# ProcessorSupport.net
KiCad netlist of a schematic drawn in Altium Designer
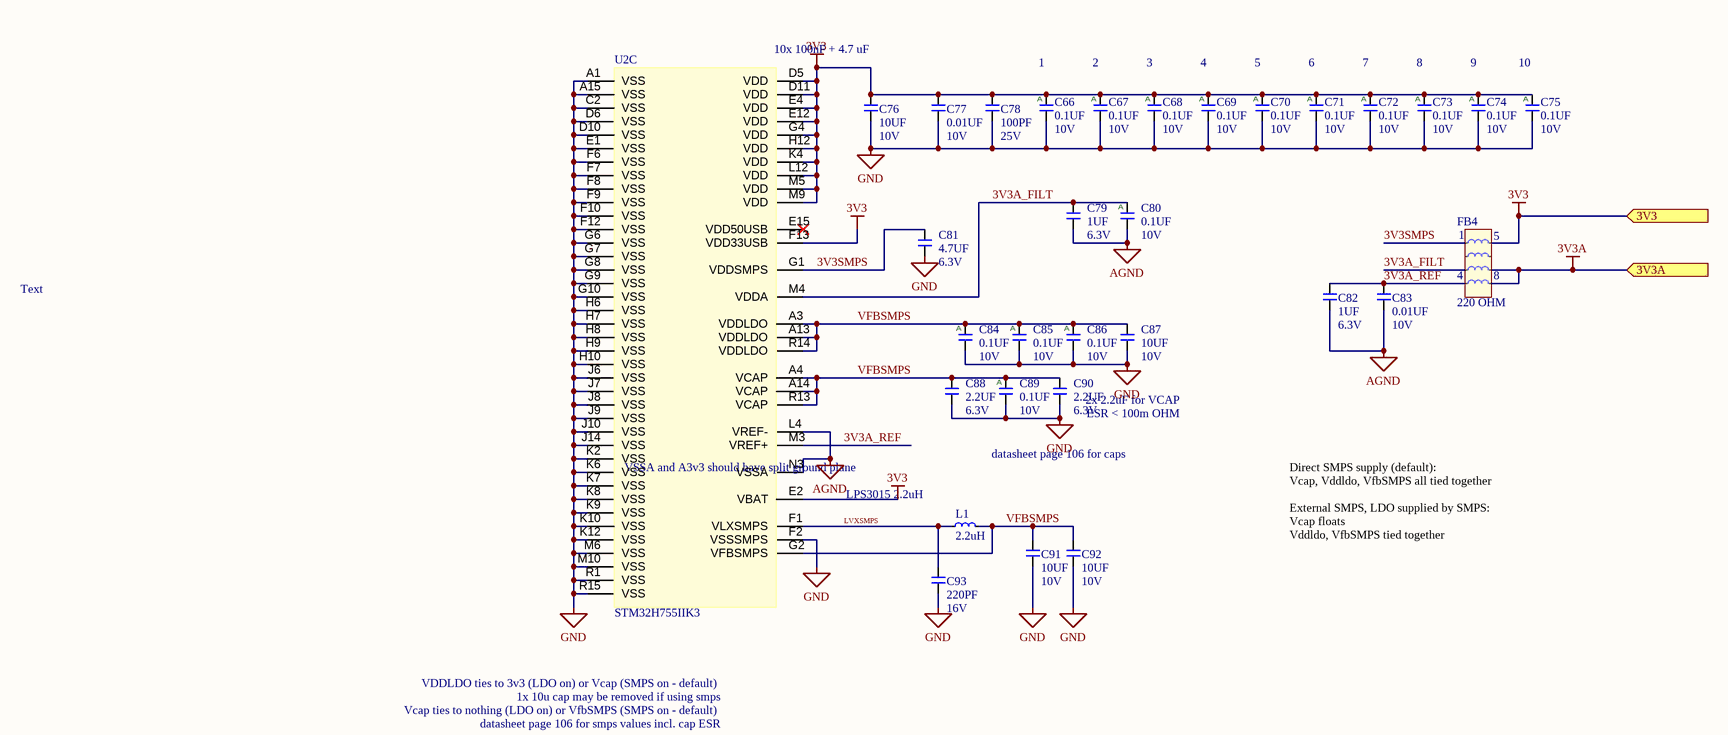
[diagram p0: ProcessorSupport.SchDoc]

(export (version "E")
  (design (tool "Eeschema 10.0.6"))
  (components
    (comp (ref "C66")
      (value "0.1UF")
      (footprint "C0201Y")
      (description "CAP, CER, X6S, 0.1uF, 10V, 10%, 0201, AUTOGRADE")
      (fields (field (name "MFG") "MURATA") (field (name "VOLTAGE") "10V") (field (name "TOLERANCE") "10%"))
      (libsource (lib "AltiumReleaseLibDB") (part "__Template_Cap_Auto"))
    )
    (comp (ref "C67")
      (value "0.1UF")
      (footprint "C0201Y")
      (description "CAP, CER, X6S, 0.1uF, 10V, 10%, 0201, AUTOGRADE")
      (fields (field (name "MFG") "MURATA") (field (name "VOLTAGE") "10V") (field (name "TOLERANCE") "10%"))
      (libsource (lib "AltiumReleaseLibDB") (part "__Template_Cap_Auto"))
    )
    (comp (ref "C68")
      (value "0.1UF")
      (footprint "C0201Y")
      (description "CAP, CER, X6S, 0.1uF, 10V, 10%, 0201, AUTOGRADE")
      (fields (field (name "MFG") "MURATA") (field (name "VOLTAGE") "10V") (field (name "TOLERANCE") "10%"))
      (libsource (lib "AltiumReleaseLibDB") (part "__Template_Cap_Auto"))
    )
    (comp (ref "C69")
      (value "0.1UF")
      (footprint "C0201Y")
      (description "CAP, CER, X6S, 0.1uF, 10V, 10%, 0201, AUTOGRADE")
      (fields (field (name "MFG") "MURATA") (field (name "VOLTAGE") "10V") (field (name "TOLERANCE") "10%"))
      (libsource (lib "AltiumReleaseLibDB") (part "__Template_Cap_Auto"))
    )
    (comp (ref "C70")
      (value "0.1UF")
      (footprint "C0201Y")
      (description "CAP, CER, X6S, 0.1uF, 10V, 10%, 0201, AUTOGRADE")
      (fields (field (name "MFG") "MURATA") (field (name "VOLTAGE") "10V") (field (name "TOLERANCE") "10%"))
      (libsource (lib "AltiumReleaseLibDB") (part "__Template_Cap_Auto"))
    )
    (comp (ref "C71")
      (value "0.1UF")
      (footprint "C0201Y")
      (description "CAP, CER, X6S, 0.1uF, 10V, 10%, 0201, AUTOGRADE")
      (fields (field (name "MFG") "MURATA") (field (name "VOLTAGE") "10V") (field (name "TOLERANCE") "10%"))
      (libsource (lib "AltiumReleaseLibDB") (part "__Template_Cap_Auto"))
    )
    (comp (ref "C72")
      (value "0.1UF")
      (footprint "C0201Y")
      (description "CAP, CER, X6S, 0.1uF, 10V, 10%, 0201, AUTOGRADE")
      (fields (field (name "MFG") "MURATA") (field (name "VOLTAGE") "10V") (field (name "TOLERANCE") "10%"))
      (libsource (lib "AltiumReleaseLibDB") (part "__Template_Cap_Auto"))
    )
    (comp (ref "C73")
      (value "0.1UF")
      (footprint "C0201Y")
      (description "CAP, CER, X6S, 0.1uF, 10V, 10%, 0201, AUTOGRADE")
      (fields (field (name "MFG") "MURATA") (field (name "VOLTAGE") "10V") (field (name "TOLERANCE") "10%"))
      (libsource (lib "AltiumReleaseLibDB") (part "__Template_Cap_Auto"))
    )
    (comp (ref "C74")
      (value "0.1UF")
      (footprint "C0201Y")
      (description "CAP, CER, X6S, 0.1uF, 10V, 10%, 0201, AUTOGRADE")
      (fields (field (name "MFG") "MURATA") (field (name "VOLTAGE") "10V") (field (name "TOLERANCE") "10%"))
      (libsource (lib "AltiumReleaseLibDB") (part "__Template_Cap_Auto"))
    )
    (comp (ref "C75")
      (value "0.1UF")
      (footprint "C0201Y")
      (description "CAP, CER, X6S, 0.1uF, 10V, 10%, 0201, AUTOGRADE")
      (fields (field (name "MFG") "MURATA") (field (name "VOLTAGE") "10V") (field (name "TOLERANCE") "10%"))
      (libsource (lib "AltiumReleaseLibDB") (part "__Template_Cap_Auto"))
    )
    (comp (ref "C76")
      (value "10UF")
      (footprint "C0402")
      (description "CAP, CER, X5R, 10uF, 10V, 20%, 0402, 0.7mm T")
      (fields (field (name "MFG") "SAMSUNG") (field (name "VOLTAGE") "10V") (field (name "TOLERANCE") "20%"))
      (libsource (lib "AltiumReleaseLibDB") (part "__Template_Cap"))
    )
    (comp (ref "C77")
      (value "0.01UF")
      (footprint "C0201Y")
      (description "CAP, CER, X7R, 0.01uF, 10V, 10%, AUTO GRADE, 0201, 0.33mm T")
      (fields (field (name "MFG") "MURATA") (field (name "VOLTAGE") "10V") (field (name "TOLERANCE") "10%"))
      (libsource (lib "AltiumReleaseLibDB") (part "__Template_Cap"))
    )
    (comp (ref "C78")
      (value "100PF")
      (footprint "C0201Y")
      (description "CAP, CER, X7R, 100pF, 25V, 10%, 0201, 0.33mm T")
      (fields (field (name "MFG") "MURATA") (field (name "VOLTAGE") "25V") (field (name "TOLERANCE") "10%"))
      (libsource (lib "AltiumReleaseLibDB") (part "__Template_Cap"))
    )
    (comp (ref "C79")
      (value "1UF")
      (footprint "C0201")
      (description "CAP, CER, X5R, 1uF, 6.3V, 20%, 0201, 0.33mm T")
      (fields (field (name "MFG") "SAMSUNG") (field (name "VOLTAGE") "6.3V") (field (name "TOLERANCE") "20%"))
      (libsource (lib "AltiumReleaseLibDB") (part "__Template_Cap"))
    )
    (comp (ref "C80")
      (value "0.1UF")
      (footprint "C0201Y")
      (description "CAP, CER, X6S, 0.1uF, 10V, 10%, 0201, AUTOGRADE")
      (fields (field (name "MFG") "MURATA") (field (name "VOLTAGE") "10V") (field (name "TOLERANCE") "10%"))
      (libsource (lib "AltiumReleaseLibDB") (part "__Template_Cap_Auto"))
    )
    (comp (ref "C81")
      (value "4.7UF")
      (footprint "C0402")
      (description "CAP, CER, X5R, 4.7uF, 20%, 6.3V, 0402, 0.65mm")
      (fields (field (name "MFG") "TDK") (field (name "VOLTAGE") "6.3V") (field (name "TOLERANCE") "20%"))
      (libsource (lib "AltiumReleaseLibDB") (part "__Template_Cap"))
    )
    (comp (ref "C82")
      (value "1UF")
      (footprint "C0201")
      (description "CAP, CER, X5R, 1uF, 6.3V, 20%, 0201, 0.33mm T")
      (fields (field (name "MFG") "SAMSUNG") (field (name "VOLTAGE") "6.3V") (field (name "TOLERANCE") "20%"))
      (libsource (lib "AltiumReleaseLibDB") (part "__Template_Cap"))
    )
    (comp (ref "C83")
      (value "0.01UF")
      (footprint "C0201Y")
      (description "CAP, CER, X7R, 0.01uF, 10V, 10%, AUTO GRADE, 0201, 0.33mm T")
      (fields (field (name "MFG") "MURATA") (field (name "VOLTAGE") "10V") (field (name "TOLERANCE") "10%"))
      (libsource (lib "AltiumReleaseLibDB") (part "__Template_Cap"))
    )
    (comp (ref "C84")
      (value "0.1UF")
      (footprint "C0201Y")
      (description "CAP, CER, X6S, 0.1uF, 10V, 10%, 0201, AUTOGRADE")
      (fields (field (name "MFG") "MURATA") (field (name "VOLTAGE") "10V") (field (name "TOLERANCE") "10%"))
      (libsource (lib "AltiumReleaseLibDB") (part "__Template_Cap_Auto"))
    )
    (comp (ref "C85")
      (value "0.1UF")
      (footprint "C0201Y")
      (description "CAP, CER, X6S, 0.1uF, 10V, 10%, 0201, AUTOGRADE")
      (fields (field (name "MFG") "MURATA") (field (name "VOLTAGE") "10V") (field (name "TOLERANCE") "10%"))
      (libsource (lib "AltiumReleaseLibDB") (part "__Template_Cap_Auto"))
    )
    (comp (ref "C86")
      (value "0.1UF")
      (footprint "C0201Y")
      (description "CAP, CER, X6S, 0.1uF, 10V, 10%, 0201, AUTOGRADE")
      (fields (field (name "MFG") "MURATA") (field (name "VOLTAGE") "10V") (field (name "TOLERANCE") "10%"))
      (libsource (lib "AltiumReleaseLibDB") (part "__Template_Cap_Auto"))
    )
    (comp (ref "C87")
      (value "10UF")
      (footprint "C0402")
      (description "CAP, CER, X5R, 10uF, 10V, 20%, 0402, 0.7mm T")
      (fields (field (name "MFG") "SAMSUNG") (field (name "VOLTAGE") "10V") (field (name "TOLERANCE") "20%"))
      (libsource (lib "AltiumReleaseLibDB") (part "__Template_Cap"))
    )
    (comp (ref "C88")
      (value "2.2UF")
      (footprint "C0201")
      (description "CAP, CER, X5R, 2.2uF, 6.3V, 20%, 0201, 0.39mm T")
      (fields (field (name "MFG") "SAMSUNG") (field (name "VOLTAGE") "6.3V") (field (name "TOLERANCE") "20%"))
      (libsource (lib "AltiumReleaseLibDB") (part "__Template_Cap"))
    )
    (comp (ref "C89")
      (value "0.1UF")
      (footprint "C0201Y")
      (description "CAP, CER, X6S, 0.1uF, 10V, 10%, 0201, AUTOGRADE")
      (fields (field (name "MFG") "MURATA") (field (name "VOLTAGE") "10V") (field (name "TOLERANCE") "10%"))
      (libsource (lib "AltiumReleaseLibDB") (part "__Template_Cap_Auto"))
    )
    (comp (ref "C90")
      (value "2.2UF")
      (footprint "C0201")
      (description "CAP, CER, X5R, 2.2uF, 6.3V, 20%, 0201, 0.39mm T")
      (fields (field (name "MFG") "SAMSUNG") (field (name "VOLTAGE") "6.3V") (field (name "TOLERANCE") "20%"))
      (libsource (lib "AltiumReleaseLibDB") (part "__Template_Cap"))
    )
    (comp (ref "C91")
      (value "10UF")
      (footprint "C0402")
      (description "CAP, CER, X5R, 10uF, 10V, 20%, 0402, 0.7mm T")
      (fields (field (name "MFG") "SAMSUNG") (field (name "VOLTAGE") "10V") (field (name "TOLERANCE") "20%"))
      (libsource (lib "AltiumReleaseLibDB") (part "__Template_Cap"))
    )
    (comp (ref "C92")
      (value "10UF")
      (footprint "C0402")
      (description "CAP, CER, X5R, 10uF, 10V, 20%, 0402, 0.7mm T")
      (fields (field (name "MFG") "SAMSUNG") (field (name "VOLTAGE") "10V") (field (name "TOLERANCE") "20%"))
      (libsource (lib "AltiumReleaseLibDB") (part "__Template_Cap"))
    )
    (comp (ref "C93")
      (value "220PF")
      (footprint "C0201Y")
      (description "CAP, CER, X7R, 220pF, 16V, 10%, 0201, 0.33mm T")
      (fields (field (name "MFG") "MURATA") (field (name "VOLTAGE") "16V") (field (name "TOLERANCE") "10%"))
      (libsource (lib "AltiumReleaseLibDB") (part "__Template_Cap"))
    )
    (comp (ref "FB4")
      (value "220 OHM")
      (footprint "FB_ARRAY_BLA31AG221SN4D")
      (description "FERRITE, BEAD, 220 OHM, 150mA, DCR 0.25 MAX, 1206")
      (fields (field (name "MFG") "Murata Electronics") (field (name "Comment") "FB_ARRAY_BLA31AG221SN4D"))
      (libsource (lib "AltiumReleaseLibDB") (part "FB_ARRAY_BLA31AG221SN4D"))
    )
    (comp (ref "L1")
      (value "2.2uH")
      (footprint "IND_LPS3015-152MRB")
      (description "IND, WIREWOUND, SHIELDED, 2.2uH, 2.1A, 20%, DCR 0.11, SMD, AUTOGRADE")
      (fields (field (name "MFG") "COILCRAFT") (field (name "TOLERANCE") "20%"))
      (libsource (lib "AltiumReleaseLibDB") (part "__Template_Inductor"))
    )
    (comp (ref "U2")
      (value "MCU_STM32H755IIK3")
      (footprint "BGS201C65P15X15_1000X1000X60")
      (description "IC, MCU, STM32H755xI, ARM, 32-BIT, 240MHZ, 128 I/O, 2MB, FLASH, 1.62V TO 3.6V, UFBGA-201")
      (fields (field (name "MFG") "STMicroelectronics") (field (name "MFG P/N") "STM32H755IIK3"))
      (libsource (lib "AltiumReleaseLibDB") (part "MCU_STM32H755IIK3"))
    )
  )
  (nets
    (net (code "1") (name "/3V3A_FILT") (class "Default")
      (node (ref "C79") (pin "1") (pintype "passive"))
      (node (ref "C80") (pin "1") (pintype "passive"))
      (node (ref "FB4") (pin "3") (pinfunction "3_3") (pintype "passive"))
      (node (ref "U2") (pin "M4") (pinfunction "VDDA_M4") (pintype "power_in"))
    )
    (net (code "2") (name "/3V3A_REF") (class "Default")
      (node (ref "C82") (pin "1") (pintype "passive"))
      (node (ref "C83") (pin "1") (pintype "passive"))
      (node (ref "FB4") (pin "4") (pinfunction "4_4") (pintype "passive"))
      (node (ref "U2") (pin "M3") (pinfunction "VREF+_M3") (pintype "power_in"))
    )
    (net (code "3") (name "/3V3SMPS") (class "Default")
      (node (ref "C81") (pin "1") (pintype "passive"))
      (node (ref "FB4") (pin "1") (pinfunction "1_1") (pintype "passive"))
      (node (ref "U2") (pin "G1") (pinfunction "VDDSMPS_G1") (pintype "power_in"))
    )
    (net (code "4") (name "/LVXSMPS") (class "Default")
      (node (ref "C93") (pin "1") (pintype "passive"))
      (node (ref "L1") (pin "1") (pintype "passive"))
      (node (ref "U2") (pin "F1") (pinfunction "VLXSMPS_F1") (pintype "power_in"))
    )
    (net (code "5") (name "/VFBSMPS") (class "Default")
      (node (ref "C84") (pin "1") (pintype "passive"))
      (node (ref "C85") (pin "1") (pintype "passive"))
      (node (ref "C86") (pin "1") (pintype "passive"))
      (node (ref "C87") (pin "1") (pintype "passive"))
      (node (ref "C88") (pin "1") (pintype "passive"))
      (node (ref "C89") (pin "1") (pintype "passive"))
      (node (ref "C90") (pin "1") (pintype "passive"))
      (node (ref "C91") (pin "2") (pintype "passive"))
      (node (ref "C92") (pin "2") (pintype "passive"))
      (node (ref "L1") (pin "2") (pintype "passive"))
      (node (ref "U2") (pin "A13") (pinfunction "VDDLDO_A13") (pintype "power_in"))
      (node (ref "U2") (pin "A14") (pinfunction "VCAP_A14") (pintype "power_in"))
      (node (ref "U2") (pin "A3") (pinfunction "VDDLDO_A3") (pintype "power_in"))
      (node (ref "U2") (pin "A4") (pinfunction "VCAP_A4") (pintype "power_in"))
      (node (ref "U2") (pin "G2") (pinfunction "VFBSMPS_G2") (pintype "power_in"))
      (node (ref "U2") (pin "R13") (pinfunction "VCAP_R13") (pintype "power_in"))
      (node (ref "U2") (pin "R14") (pinfunction "VDDLDO_R14") (pintype "power_in"))
    )
    (net (code "6") (name "3V3") (class "Default")
      (node (ref "C66") (pin "1") (pintype "passive"))
      (node (ref "C67") (pin "1") (pintype "passive"))
      (node (ref "C68") (pin "1") (pintype "passive"))
      (node (ref "C69") (pin "1") (pintype "passive"))
      (node (ref "C70") (pin "1") (pintype "passive"))
      (node (ref "C71") (pin "1") (pintype "passive"))
      (node (ref "C72") (pin "1") (pintype "passive"))
      (node (ref "C73") (pin "1") (pintype "passive"))
      (node (ref "C74") (pin "1") (pintype "passive"))
      (node (ref "C75") (pin "1") (pintype "passive"))
      (node (ref "C76") (pin "1") (pintype "passive"))
      (node (ref "C77") (pin "1") (pintype "passive"))
      (node (ref "C78") (pin "1") (pintype "passive"))
      (node (ref "FB4") (pin "5") (pinfunction "5_5") (pintype "passive"))
      (node (ref "U2") (pin "D11") (pinfunction "VDD_D11") (pintype "power_in"))
      (node (ref "U2") (pin "D5") (pinfunction "VDD_D5") (pintype "power_in"))
      (node (ref "U2") (pin "E12") (pinfunction "VDD_E12") (pintype "power_in"))
      (node (ref "U2") (pin "E2") (pinfunction "VBAT_E2") (pintype "power_in"))
      (node (ref "U2") (pin "E4") (pinfunction "VDD_E4") (pintype "power_in"))
      (node (ref "U2") (pin "F13") (pinfunction "VDD33USB_F13") (pintype "power_in"))
      (node (ref "U2") (pin "G4") (pinfunction "VDD_G4") (pintype "power_in"))
      (node (ref "U2") (pin "H12") (pinfunction "VDD_H12") (pintype "power_in"))
      (node (ref "U2") (pin "K4") (pinfunction "VDD_K4") (pintype "power_in"))
      (node (ref "U2") (pin "L12") (pinfunction "VDD_L12") (pintype "power_in"))
      (node (ref "U2") (pin "M5") (pinfunction "VDD_M5") (pintype "power_in"))
      (node (ref "U2") (pin "M9") (pinfunction "VDD_M9") (pintype "power_in"))
    )
    (net (code "7") (name "3V3A") (class "Default")
      (node (ref "FB4") (pin "7") (pinfunction "7_7") (pintype "passive"))
      (node (ref "FB4") (pin "8") (pinfunction "8_8") (pintype "passive"))
    )
    (net (code "8") (name "AGND") (class "Default")
      (node (ref "C79") (pin "2") (pintype "passive"))
      (node (ref "C80") (pin "2") (pintype "passive"))
      (node (ref "C82") (pin "2") (pintype "passive"))
      (node (ref "C83") (pin "2") (pintype "passive"))
      (node (ref "U2") (pin "L4") (pinfunction "VREF-_L4") (pintype "power_in"))
      (node (ref "U2") (pin "N3") (pinfunction "VSSA_N3") (pintype "power_in"))
    )
    (net (code "9") (name "GND") (class "Default")
      (node (ref "C66") (pin "2") (pintype "passive"))
      (node (ref "C67") (pin "2") (pintype "passive"))
      (node (ref "C68") (pin "2") (pintype "passive"))
      (node (ref "C69") (pin "2") (pintype "passive"))
      (node (ref "C70") (pin "2") (pintype "passive"))
      (node (ref "C71") (pin "2") (pintype "passive"))
      (node (ref "C72") (pin "2") (pintype "passive"))
      (node (ref "C73") (pin "2") (pintype "passive"))
      (node (ref "C74") (pin "2") (pintype "passive"))
      (node (ref "C75") (pin "2") (pintype "passive"))
      (node (ref "C76") (pin "2") (pintype "passive"))
      (node (ref "C77") (pin "2") (pintype "passive"))
      (node (ref "C78") (pin "2") (pintype "passive"))
      (node (ref "C81") (pin "2") (pintype "passive"))
      (node (ref "C84") (pin "2") (pintype "passive"))
      (node (ref "C85") (pin "2") (pintype "passive"))
      (node (ref "C86") (pin "2") (pintype "passive"))
      (node (ref "C87") (pin "2") (pintype "passive"))
      (node (ref "C88") (pin "2") (pintype "passive"))
      (node (ref "C89") (pin "2") (pintype "passive"))
      (node (ref "C90") (pin "2") (pintype "passive"))
      (node (ref "C91") (pin "1") (pintype "passive"))
      (node (ref "C92") (pin "1") (pintype "passive"))
      (node (ref "C93") (pin "2") (pintype "passive"))
      (node (ref "U2") (pin "A1") (pinfunction "VSS_A1") (pintype "power_in"))
      (node (ref "U2") (pin "A15") (pinfunction "VSS_A15") (pintype "power_in"))
      (node (ref "U2") (pin "C2") (pinfunction "VSS_C2") (pintype "power_in"))
      (node (ref "U2") (pin "D10") (pinfunction "VSS_D10") (pintype "power_in"))
      (node (ref "U2") (pin "D6") (pinfunction "VSS_D6") (pintype "power_in"))
      (node (ref "U2") (pin "E1") (pinfunction "VSS_E1") (pintype "power_in"))
      (node (ref "U2") (pin "F10") (pinfunction "VSS_F10") (pintype "power_in"))
      (node (ref "U2") (pin "F12") (pinfunction "VSS_F12") (pintype "power_in"))
      (node (ref "U2") (pin "F2") (pinfunction "VSSSMPS_F2") (pintype "power_in"))
      (node (ref "U2") (pin "F6") (pinfunction "VSS_F6") (pintype "power_in"))
      (node (ref "U2") (pin "F7") (pinfunction "VSS_F7") (pintype "power_in"))
      (node (ref "U2") (pin "F8") (pinfunction "VSS_F8") (pintype "power_in"))
      (node (ref "U2") (pin "F9") (pinfunction "VSS_F9") (pintype "power_in"))
      (node (ref "U2") (pin "G10") (pinfunction "VSS_G10") (pintype "power_in"))
      (node (ref "U2") (pin "G6") (pinfunction "VSS_G6") (pintype "power_in"))
      (node (ref "U2") (pin "G7") (pinfunction "VSS_G7") (pintype "power_in"))
      (node (ref "U2") (pin "G8") (pinfunction "VSS_G8") (pintype "power_in"))
      (node (ref "U2") (pin "G9") (pinfunction "VSS_G9") (pintype "power_in"))
      (node (ref "U2") (pin "H10") (pinfunction "VSS_H10") (pintype "power_in"))
      (node (ref "U2") (pin "H6") (pinfunction "VSS_H6") (pintype "power_in"))
      (node (ref "U2") (pin "H7") (pinfunction "VSS_H7") (pintype "power_in"))
      (node (ref "U2") (pin "H8") (pinfunction "VSS_H8") (pintype "power_in"))
      (node (ref "U2") (pin "H9") (pinfunction "VSS_H9") (pintype "power_in"))
      (node (ref "U2") (pin "J10") (pinfunction "VSS_J10") (pintype "power_in"))
      (node (ref "U2") (pin "J14") (pinfunction "VSS_J14") (pintype "power_in"))
      (node (ref "U2") (pin "J6") (pinfunction "VSS_J6") (pintype "power_in"))
      (node (ref "U2") (pin "J7") (pinfunction "VSS_J7") (pintype "power_in"))
      (node (ref "U2") (pin "J8") (pinfunction "VSS_J8") (pintype "power_in"))
      (node (ref "U2") (pin "J9") (pinfunction "VSS_J9") (pintype "power_in"))
      (node (ref "U2") (pin "K10") (pinfunction "VSS_K10") (pintype "power_in"))
      (node (ref "U2") (pin "K12") (pinfunction "VSS_K12") (pintype "power_in"))
      (node (ref "U2") (pin "K2") (pinfunction "VSS_K2") (pintype "power_in"))
      (node (ref "U2") (pin "K6") (pinfunction "VSS_K6") (pintype "power_in"))
      (node (ref "U2") (pin "K7") (pinfunction "VSS_K7") (pintype "power_in"))
      (node (ref "U2") (pin "K8") (pinfunction "VSS_K8") (pintype "power_in"))
      (node (ref "U2") (pin "K9") (pinfunction "VSS_K9") (pintype "power_in"))
      (node (ref "U2") (pin "M10") (pinfunction "VSS_M10") (pintype "power_in"))
      (node (ref "U2") (pin "M6") (pinfunction "VSS_M6") (pintype "power_in"))
      (node (ref "U2") (pin "R1") (pinfunction "VSS_R1") (pintype "power_in"))
      (node (ref "U2") (pin "R15") (pinfunction "VSS_R15") (pintype "power_in"))
    )
    (net (code "10") (name "unconnected-(FB4-Pad2)") (class "Default")
      (node (ref "FB4") (pin "2") (pinfunction "2_2") (pintype "passive"))
    )
    (net (code "11") (name "unconnected-(FB4-Pad6)") (class "Default")
      (node (ref "FB4") (pin "6") (pinfunction "6_6") (pintype "passive"))
    )
    (net (code "12") (name "unconnected-(U2C-VDD50USB-PadE15)") (class "Default")
      (node (ref "U2") (pin "E15") (pinfunction "VDD50USB_E15") (pintype "power_in+no_connect"))
    )
  )
)
